# POWER.net
KiCad netlist of a schematic drawn in Altium Designer
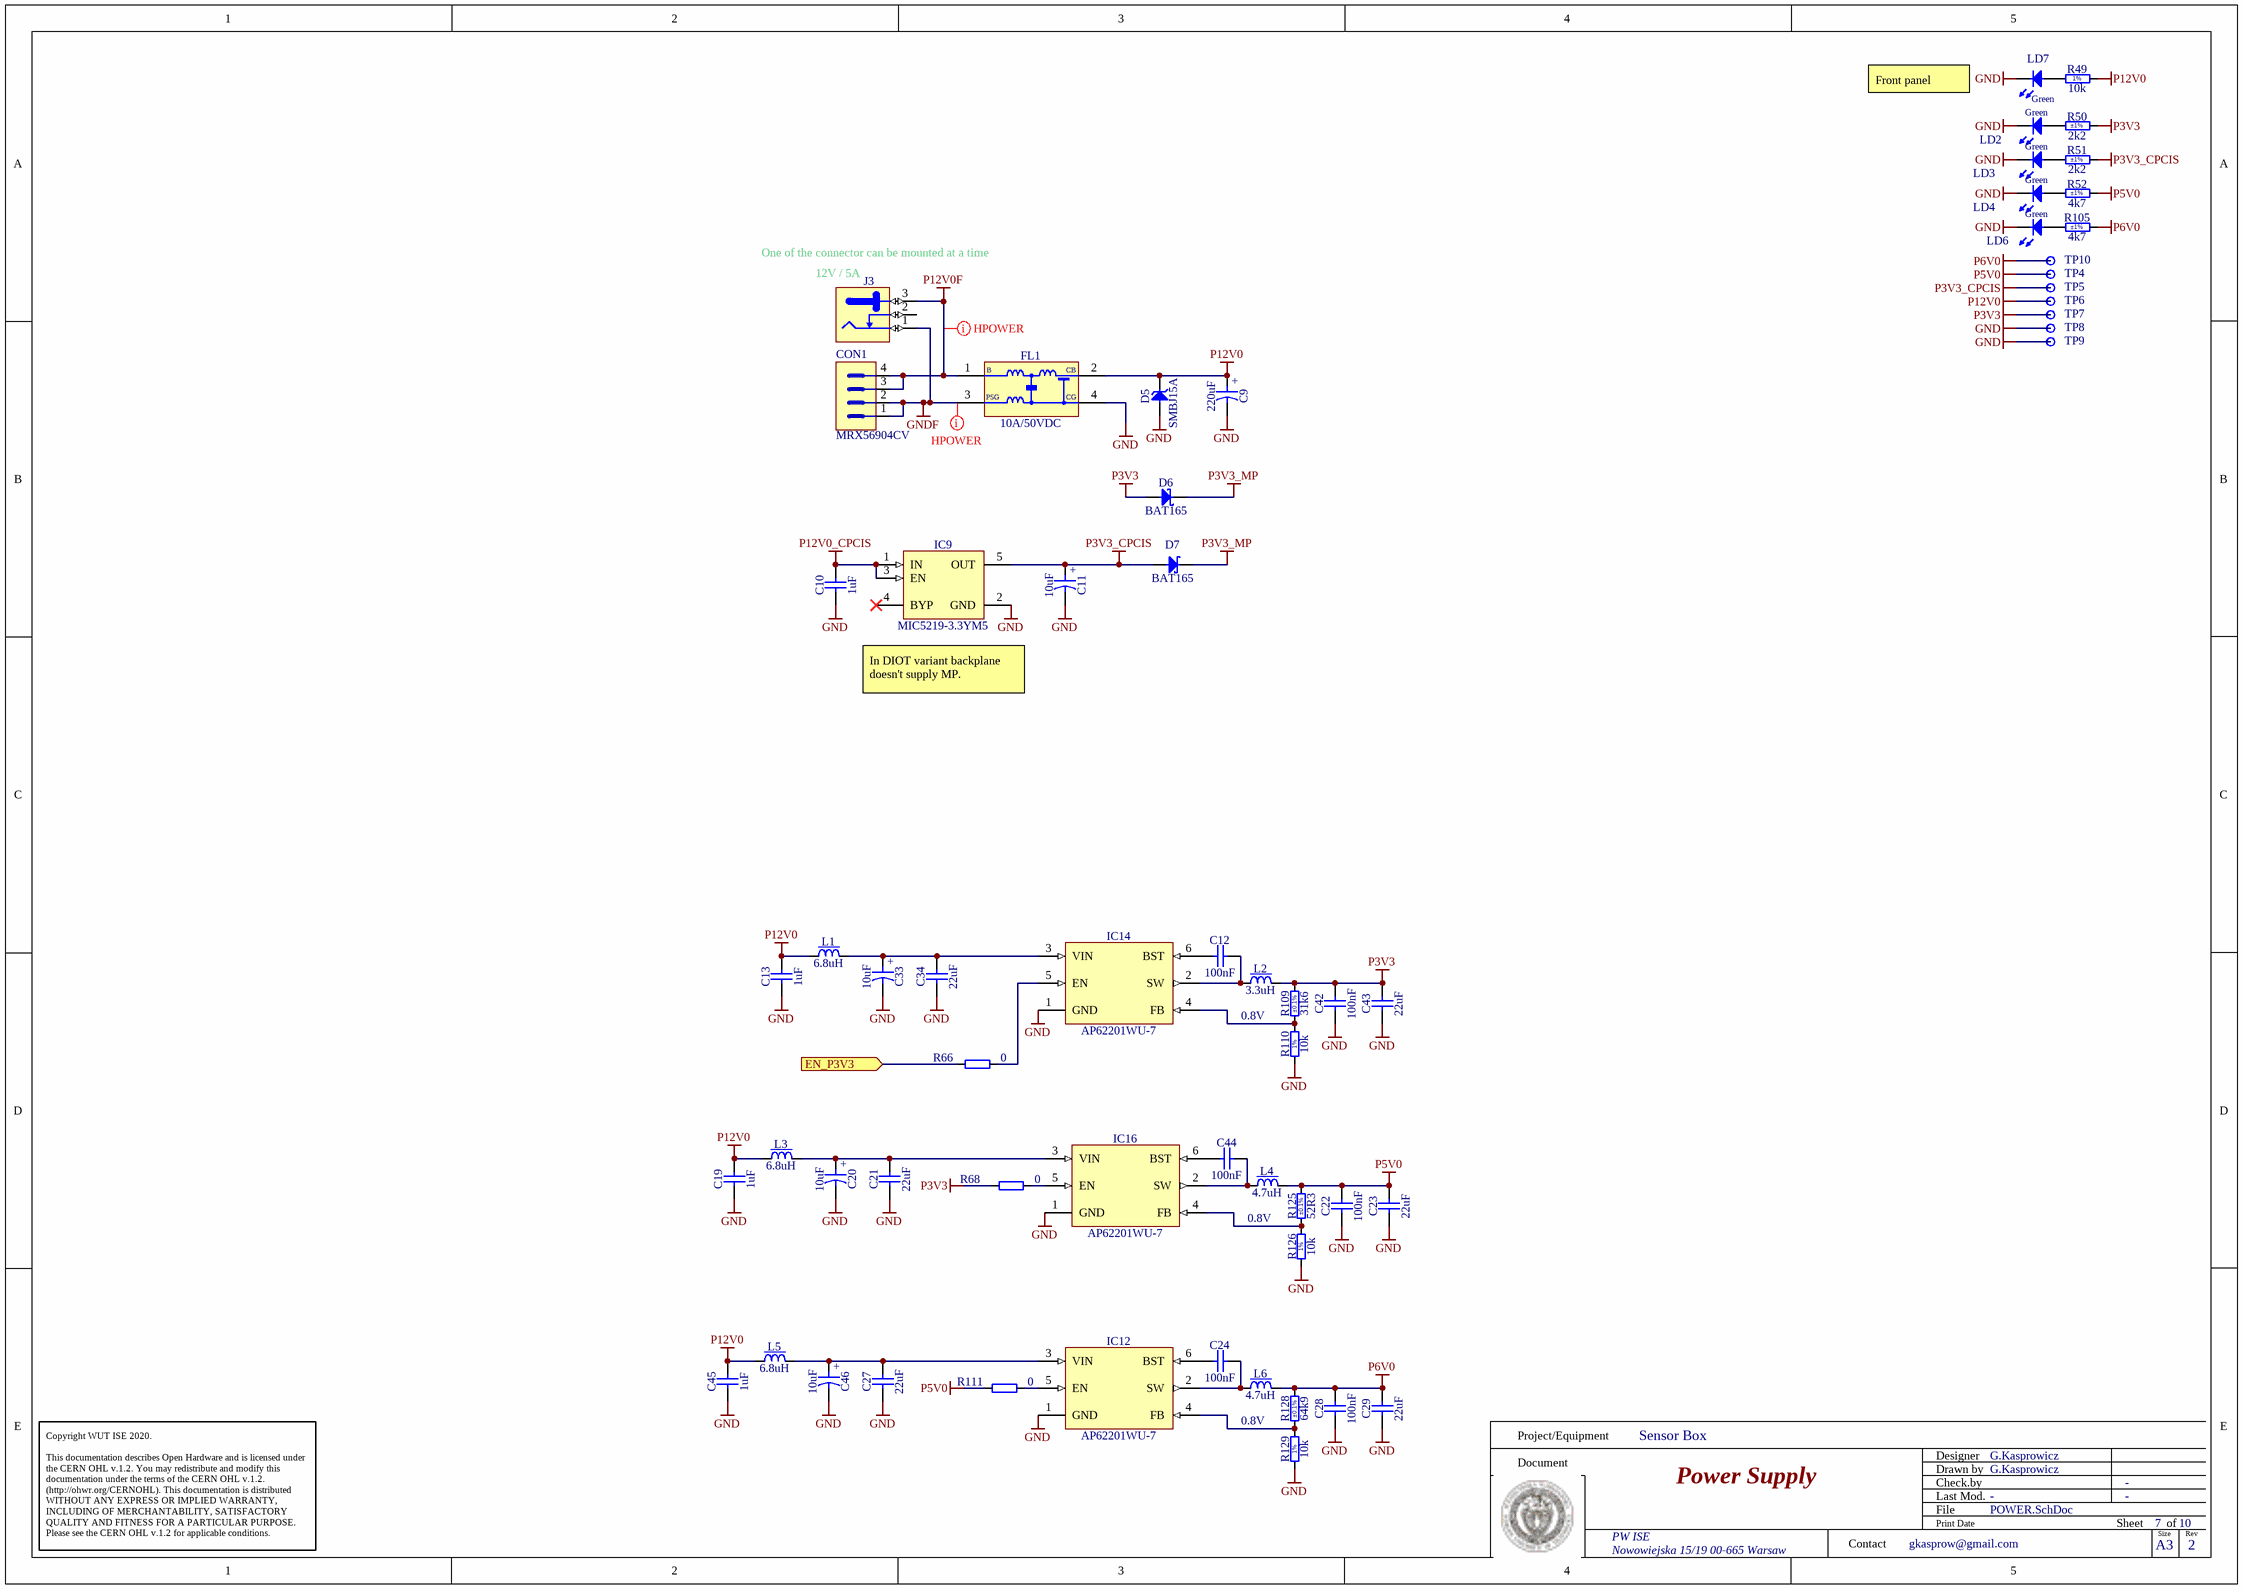
[diagram p0: POWER.SchDoc]

(export (version "E")
  (design (tool "Eeschema 10.0.6"))
  (components
    (comp (ref "C9")
      (value "220uF")
      (footprint "CAPAE830X620N")
      (description "Polarised capacitor")
      (fields
        (field (name "PART NUMBER") "CAE830-620_220UF_16V_20%")
        (field (name "VOLTAGE") "16V")
        (field (name "AUTHOR") "CERN DEM JLC")
      )
      (libsource (lib "Capacitors") (part "Capacitor - polarized"))
    )
    (comp (ref "C10")
      (value "1uF")
      (footprint "CAPC1608X87N")
      (description "Non-polarised capacitor")
      (fields
        (field (name "PART NUMBER") "CC0603_1UF_25V_10%_X7R")
        (field (name "VOLTAGE") "25V")
        (field (name "AUTHOR") "CERN DEM JLC")
      )
      (libsource (lib "Capacitors") (part "Capacitor - non polarized"))
    )
    (comp (ref "C11")
      (value "10uF")
      (footprint "CAPMP3216X180N")
      (description "Polarised capacitor")
      (fields
        (field (name "PART NUMBER") "CTE3216-18_10UF_16V_20%_AVX_TCJ")
        (field (name "VOLTAGE") "16V")
        (field (name "AUTHOR") "CERN DEM JLC")
      )
      (libsource (lib "Capacitors") (part "Capacitor - polarized"))
    )
    (comp (ref "C12")
      (value "100nF")
      (footprint "CAPC1005X55N")
      (description "Non-polarised capacitor")
      (fields
        (field (name "PART NUMBER") "CC0402_100NF_16V_10%_X5R")
        (field (name "VOLTAGE") "16V")
        (field (name "AUTHOR") "CERN DEM JLC")
      )
      (libsource (lib "Capacitors") (part "Capacitor - non polarized"))
    )
    (comp (ref "C13")
      (value "1uF")
      (footprint "CAPC1608X87N")
      (description "Non-polarised capacitor")
      (fields
        (field (name "PART NUMBER") "CC0603_1UF_25V_10%_X7R")
        (field (name "VOLTAGE") "25V")
        (field (name "AUTHOR") "CERN DEM JLC")
      )
      (libsource (lib "Capacitors") (part "Capacitor - non polarized"))
    )
    (comp (ref "C19")
      (value "1uF")
      (footprint "CAPC1608X87N")
      (description "Non-polarised capacitor")
      (fields
        (field (name "PART NUMBER") "CC0603_1UF_25V_10%_X7R")
        (field (name "VOLTAGE") "25V")
        (field (name "AUTHOR") "CERN DEM JLC")
      )
      (libsource (lib "Capacitors") (part "Capacitor - non polarized"))
    )
    (comp (ref "C20")
      (value "10uF")
      (footprint "CAPMP3216X180N")
      (description "Polarised capacitor")
      (fields
        (field (name "PART NUMBER") "CTE3216-18_10UF_16V_20%_AVX_TCJ")
        (field (name "VOLTAGE") "16V")
        (field (name "AUTHOR") "CERN DEM JLC")
      )
      (libsource (lib "Capacitors") (part "Capacitor - polarized"))
    )
    (comp (ref "C21")
      (value "22uF")
      (footprint "CAPC2012X135N")
      (description "Non-polarised capacitor")
      (fields
        (field (name "PART NUMBER") "CC0805_22UF_16V_10%_X5R")
        (field (name "VOLTAGE") "16V")
        (field (name "AUTHOR") "CERN DEM JLC")
      )
      (libsource (lib "Capacitors") (part "Capacitor - non polarized"))
    )
    (comp (ref "C22")
      (value "100nF")
      (footprint "CAPC1005X55N")
      (description "Non-polarised capacitor")
      (fields
        (field (name "PART NUMBER") "CC0402_100NF_16V_10%_X5R")
        (field (name "VOLTAGE") "16V")
        (field (name "AUTHOR") "CERN DEM JLC")
      )
      (libsource (lib "Capacitors") (part "Capacitor - non polarized"))
    )
    (comp (ref "C23")
      (value "22uF")
      (footprint "CAPC2012X135N")
      (description "Non-polarised capacitor")
      (fields
        (field (name "PART NUMBER") "CC0805_22UF_16V_10%_X5R")
        (field (name "VOLTAGE") "16V")
        (field (name "AUTHOR") "CERN DEM JLC")
      )
      (libsource (lib "Capacitors") (part "Capacitor - non polarized"))
    )
    (comp (ref "C24")
      (value "100nF")
      (footprint "CAPC1005X55N")
      (description "Non-polarised capacitor")
      (fields
        (field (name "PART NUMBER") "CC0402_100NF_16V_10%_X5R")
        (field (name "VOLTAGE") "16V")
        (field (name "AUTHOR") "CERN DEM JLC")
      )
      (libsource (lib "Capacitors") (part "Capacitor - non polarized"))
    )
    (comp (ref "C27")
      (value "22uF")
      (footprint "CAPC2012X135N")
      (description "Non-polarised capacitor")
      (fields
        (field (name "PART NUMBER") "CC0805_22UF_16V_10%_X5R")
        (field (name "VOLTAGE") "16V")
        (field (name "AUTHOR") "CERN DEM JLC")
      )
      (libsource (lib "Capacitors") (part "Capacitor - non polarized"))
    )
    (comp (ref "C28")
      (value "100nF")
      (footprint "CAPC1005X55N")
      (description "Non-polarised capacitor")
      (fields
        (field (name "PART NUMBER") "CC0402_100NF_16V_10%_X5R")
        (field (name "VOLTAGE") "16V")
        (field (name "AUTHOR") "CERN DEM JLC")
      )
      (libsource (lib "Capacitors") (part "Capacitor - non polarized"))
    )
    (comp (ref "C29")
      (value "22uF")
      (footprint "CAPC2012X135N")
      (description "Non-polarised capacitor")
      (fields
        (field (name "PART NUMBER") "CC0805_22UF_16V_10%_X5R")
        (field (name "VOLTAGE") "16V")
        (field (name "AUTHOR") "CERN DEM JLC")
      )
      (libsource (lib "Capacitors") (part "Capacitor - non polarized"))
    )
    (comp (ref "C33")
      (value "10uF")
      (footprint "CAPMP3216X180N")
      (description "Polarised capacitor")
      (fields
        (field (name "PART NUMBER") "CTE3216-18_10UF_16V_20%_AVX_TCJ")
        (field (name "VOLTAGE") "16V")
        (field (name "AUTHOR") "CERN DEM JLC")
      )
      (libsource (lib "Capacitors") (part "Capacitor - polarized"))
    )
    (comp (ref "C34")
      (value "22uF")
      (footprint "CAPC2012X135N")
      (description "Non-polarised capacitor")
      (fields
        (field (name "PART NUMBER") "CC0805_22UF_16V_10%_X5R")
        (field (name "VOLTAGE") "16V")
        (field (name "AUTHOR") "CERN DEM JLC")
      )
      (libsource (lib "Capacitors") (part "Capacitor - non polarized"))
    )
    (comp (ref "C42")
      (value "100nF")
      (footprint "CAPC1005X55N")
      (description "Non-polarised capacitor")
      (fields
        (field (name "PART NUMBER") "CC0402_100NF_16V_10%_X5R")
        (field (name "VOLTAGE") "16V")
        (field (name "AUTHOR") "CERN DEM JLC")
      )
      (libsource (lib "Capacitors") (part "Capacitor - non polarized"))
    )
    (comp (ref "C43")
      (value "22uF")
      (footprint "CAPC2012X135N")
      (description "Non-polarised capacitor")
      (fields
        (field (name "PART NUMBER") "CC0805_22UF_16V_10%_X5R")
        (field (name "VOLTAGE") "16V")
        (field (name "AUTHOR") "CERN DEM JLC")
      )
      (libsource (lib "Capacitors") (part "Capacitor - non polarized"))
    )
    (comp (ref "C44")
      (value "100nF")
      (footprint "CAPC1005X55N")
      (description "Non-polarised capacitor")
      (fields
        (field (name "PART NUMBER") "CC0402_100NF_16V_10%_X5R")
        (field (name "VOLTAGE") "16V")
        (field (name "AUTHOR") "CERN DEM JLC")
      )
      (libsource (lib "Capacitors") (part "Capacitor - non polarized"))
    )
    (comp (ref "C45")
      (value "1uF")
      (footprint "CAPC1608X87N")
      (description "Non-polarised capacitor")
      (fields
        (field (name "PART NUMBER") "CC0603_1UF_25V_10%_X7R")
        (field (name "VOLTAGE") "25V")
        (field (name "AUTHOR") "CERN DEM JLC")
      )
      (libsource (lib "Capacitors") (part "Capacitor - non polarized"))
    )
    (comp (ref "C46")
      (value "10uF")
      (footprint "CAPMP3216X180N")
      (description "Polarised capacitor")
      (fields
        (field (name "PART NUMBER") "CTE3216-18_10UF_16V_20%_AVX_TCJ")
        (field (name "VOLTAGE") "16V")
        (field (name "AUTHOR") "CERN DEM JLC")
      )
      (libsource (lib "Capacitors") (part "Capacitor - polarized"))
    )
    (comp (ref "CON1")
      (value "MRX56904CV")
      (footprint "MRX56904CV")
      (description "4.2mm cripm terminal header")
      (libsource (lib "Magneto") (part "CON_CRIMP_4.2mm_RA_4"))
    )
    (comp (ref "D5")
      (value "SMBJ15A")
      (footprint "DIOM5336X265N")
      (description "Zener Diode")
      (fields
        (field (name "VOLTAGE") "15V")
        (field (name "POWER") "600W")
        (field (name "AUTHOR") "CERN DEM JLC")
      )
      (libsource (lib "ICs And Semiconductors") (part "Diode Zener"))
    )
    (comp (ref "D6")
      (value "BAT165")
      (footprint "SOD2512X110N")
      (description "Schottky Diode")
      (fields
        (field (name "VOLTAGE") "40V")
        (field (name "POWER") "750mA")
        (field (name "AUTHOR") "CERN DEM JLC")
      )
      (libsource (lib "ICs And Semiconductors") (part "Diode Schottky"))
    )
    (comp (ref "D7")
      (value "BAT165")
      (footprint "SOD2512X110N")
      (description "Schottky Diode")
      (fields
        (field (name "MANUFACTURER") "INFINEON")
        (field (name "VOLTAGE") "40V")
        (field (name "AUTHOR") "CERN DEM JLC")
      )
      (libsource (lib "ICs And Semiconductors") (part "Diode Schottky"))
    )
    (comp (ref "FL1")
      (value "10A/50VDC")
      (footprint "FIL_MURATA_BNX02")
      (description "Block Type EMIFIL (LC Combined)")
      (fields
        (field (name "PART NUMBER") "FIL_MURATA_BNX022-01L")
        (field (name "MANUFACTURER") "MURATA")
        (field (name "AUTHOR") "CERN DEM JLC")
      )
      (libsource (lib "Inductors & Transformers") (part "FIL_MURATA_BNX02"))
    )
    (comp (ref "IC9")
      (value "MIC5219-3.3YM5")
      (footprint "SOT95P280X145-5N")
      (description "500mA Peak Output LDO Regulator")
      (fields (field (name "MANUFACTURER") "MICROCHIP TECHNOLOGY") (field (name "AUTHOR") "CERN DEM WB"))
      (libsource (lib "ICs And Semiconductors") (part "MIC5219-X.XYM5"))
    )
    (comp (ref "IC12")
      (value "AP62201WU-7")
      (footprint "SOT95P280X100-6N")
      (description "4.2V TO 18V INPUT, 2A LOW IQ SYNCHRONOUS BUCK CONVERTER")
      (fields (field (name "MANUFACTURER") "DIODES INCORPORATED") (field (name "AUTHOR") "CERN DEM HF"))
      (libsource (lib "Magneto") (part "AP62201WU-7"))
    )
    (comp (ref "IC14")
      (value "AP62201WU-7")
      (footprint "SOT95P280X100-6N")
      (description "4.2V TO 18V INPUT, 2A LOW IQ SYNCHRONOUS BUCK CONVERTER")
      (fields (field (name "MANUFACTURER") "DIODES INCORPORATED") (field (name "AUTHOR") "CERN DEM HF"))
      (libsource (lib "Magneto") (part "AP62201WU-7"))
    )
    (comp (ref "IC16")
      (value "AP62201WU-7")
      (footprint "SOT95P280X100-6N")
      (description "4.2V TO 18V INPUT, 2A LOW IQ SYNCHRONOUS BUCK CONVERTER")
      (fields (field (name "MANUFACTURER") "DIODES INCORPORATED") (field (name "AUTHOR") "CERN DEM HF"))
      (libsource (lib "Magneto") (part "AP62201WU-7"))
    )
    (comp (ref "J3")
      (value "Jack")
      (footprint "SWITCHCRAFT_L712RA")
      (description "24V /3. 5A, 2.1mm Diameter Pin, SMD DC Power Supply Connector With  Break Contact")
      (fields
        (field (name "PART NUMBER") "SWITCHCRAFT_L712RA")
        (field (name "MANUFACTURER") "SWITCHCRAFT")
        (field (name "AUTHOR") "GK")
      )
      (libsource (lib "LIBRARY_SCH") (part "CON_DC_5A_THT_RA"))
    )
    (comp (ref "L1")
      (value "6.8uH")
      (footprint "IND_COILCRAFT_XAL4030")
      (description "Inductor With Core")
      (fields
        (field (name "PART NUMBER") "IND_6.8UH_20%_COILCRAFT_XAL4030")
        (field (name "POWER") "3A")
        (field (name "AUTHOR") "CERN DEM MR")
      )
      (libsource (lib "Inductors & Transformers") (part "Inductor With Magnetic core"))
    )
    (comp (ref "L2")
      (value "3.3uH")
      (footprint "IND_WURTH_WE-TPC_4828")
      (description "Inductor With Core")
      (fields
        (field (name "PART NUMBER") "IND_3.3UH_30%_WURTH_WE-TPC_744043003")
        (field (name "POWER") "2.15A")
        (field (name "AUTHOR") "CERN DEM JLC")
      )
      (libsource (lib "Inductors & Transformers") (part "Inductor With Magnetic core"))
    )
    (comp (ref "L3")
      (value "6.8uH")
      (footprint "IND_COILCRAFT_XAL4030")
      (description "Inductor With Core")
      (fields
        (field (name "PART NUMBER") "IND_6.8UH_20%_COILCRAFT_XAL4030")
        (field (name "POWER") "3A")
        (field (name "AUTHOR") "CERN DEM MR")
      )
      (libsource (lib "Inductors & Transformers") (part "Inductor With Magnetic core"))
    )
    (comp (ref "L4")
      (value "4.7uH")
      (footprint "IND_WURTH_WE-SPC-4838")
      (description "Inductor With Core")
      (fields
        (field (name "PART NUMBER") "IND_4.7UH_20%_WURTH_WE-SPC_74408943047")
        (field (name "POWER") "2.2A")
        (field (name "AUTHOR") "CERN DEM JLC")
      )
      (libsource (lib "Inductors & Transformers") (part "Inductor With Magnetic core"))
    )
    (comp (ref "L5")
      (value "6.8uH")
      (footprint "IND_COILCRAFT_XAL4030")
      (description "Inductor With Core")
      (fields
        (field (name "PART NUMBER") "IND_6.8UH_20%_COILCRAFT_XAL4030")
        (field (name "POWER") "3A")
        (field (name "AUTHOR") "CERN DEM MR")
      )
      (libsource (lib "Inductors & Transformers") (part "Inductor With Magnetic core"))
    )
    (comp (ref "L6")
      (value "4.7uH")
      (footprint "IND_WURTH_WE-SPC-4838")
      (description "Inductor With Core")
      (fields
        (field (name "PART NUMBER") "IND_4.7UH_20%_WURTH_WE-SPC_74408943047")
        (field (name "POWER") "2.2A")
        (field (name "AUTHOR") "CERN DEM JLC")
      )
      (libsource (lib "Inductors & Transformers") (part "Inductor With Magnetic core"))
    )
    (comp (ref "LD2")
      (value "Green")
      (footprint "LED_KINGBRIGHT_KPH-1608CGCK")
      (description "LED Green 1C 2A")
      (fields
        (field (name "PART NUMBER") "LED_KINGBRIGHT_KPH-1608CGCK")
        (field (name "MANUFACTURER") "KINGBRIGHT")
        (field (name "AUTHOR") "CERN DEM JLC")
      )
      (libsource (lib "ICs And Semiconductors") (part "LED Green 1C 2A"))
    )
    (comp (ref "LD3")
      (value "Green")
      (footprint "LED_KINGBRIGHT_KPH-1608CGCK")
      (description "LED Green 1C 2A")
      (fields
        (field (name "PART NUMBER") "LED_KINGBRIGHT_KPH-1608CGCK")
        (field (name "MANUFACTURER") "KINGBRIGHT")
        (field (name "AUTHOR") "CERN DEM JLC")
      )
      (libsource (lib "ICs And Semiconductors") (part "LED Green 1C 2A"))
    )
    (comp (ref "LD4")
      (value "Green")
      (footprint "LED_KINGBRIGHT_KPH-1608CGCK")
      (description "LED Green 1C 2A")
      (fields
        (field (name "PART NUMBER") "LED_KINGBRIGHT_KPH-1608CGCK")
        (field (name "MANUFACTURER") "KINGBRIGHT")
        (field (name "AUTHOR") "CERN DEM JLC")
      )
      (libsource (lib "ICs And Semiconductors") (part "LED Green 1C 2A"))
    )
    (comp (ref "LD6")
      (value "Green")
      (footprint "LED_KINGBRIGHT_KPH-1608CGCK")
      (description "LED Green 1C 2A")
      (fields
        (field (name "PART NUMBER") "LED_KINGBRIGHT_KPH-1608CGCK")
        (field (name "MANUFACTURER") "KINGBRIGHT")
        (field (name "AUTHOR") "CERN DEM JLC")
      )
      (libsource (lib "ICs And Semiconductors") (part "LED Green 1C 2A"))
    )
    (comp (ref "LD7")
      (value "Green")
      (footprint "LED_DIALIGHT_555-230")
      (description "LED Green 1C 2A")
      (fields
        (field (name "PART NUMBER") "LED_DIALIGHT_555-2301F")
        (field (name "MANUFACTURER") "DIALIGHT")
        (field (name "AUTHOR") "CERN DEM JMW")
      )
      (libsource (lib "ICs And Semiconductors") (part "LED Green 1C 2A"))
    )
    (comp (ref "R49")
      (value "10k")
      (footprint "RESC1005X40N")
      (description "Resistor - 1%")
      (fields
        (field (name "PART NUMBER") "R0402_10K_1%_0.0625W_100PPM")
        (field (name "POWER") "0.0625W")
        (field (name "AUTHOR") "CERN DEM JLC")
      )
      (libsource (lib "Resistors") (part "Resistor - 1%"))
    )
    (comp (ref "R50")
      (value "2k2")
      (footprint "RESC1005X40N")
      (description "Resistor - 1%")
      (fields
        (field (name "TOLERANCE") "±1%")
        (field (name "PART NUMBER") "R0402_2K2_1%_0.0625W_100PPM")
        (field (name "POWER") "0.0625W")
        (field (name "AUTHOR") "CERN DEM JLC")
      )
      (libsource (lib "Resistors") (part "Resistor - 1%"))
    )
    (comp (ref "R51")
      (value "2k2")
      (footprint "RESC1005X40N")
      (description "Resistor - 1%")
      (fields
        (field (name "TOLERANCE") "±1%")
        (field (name "PART NUMBER") "R0402_2K2_1%_0.0625W_100PPM")
        (field (name "POWER") "0.0625W")
        (field (name "AUTHOR") "CERN DEM JLC")
      )
      (libsource (lib "Resistors") (part "Resistor - 1%"))
    )
    (comp (ref "R52")
      (value "4k7")
      (footprint "RESC1005X40N")
      (description "Resistor - 1%")
      (fields
        (field (name "TOLERANCE") "±1%")
        (field (name "PART NUMBER") "R0402_4K7_1%_0.0625W_100PPM")
        (field (name "POWER") "0.0625W")
        (field (name "AUTHOR") "CERN DEM JLC")
      )
      (libsource (lib "Resistors") (part "Resistor - 1%"))
    )
    (comp (ref "R66")
      (value "0")
      (footprint "RESC1005X40N")
      (description "Resistor")
      (fields
        (field (name "PART NUMBER") "R0402_0R_JUMPER")
        (field (name "MANUFACTURER") "GENERIC")
        (field (name "AUTHOR") "CERN DEM JLC")
      )
      (libsource (lib "Resistors") (part "Resistor"))
    )
    (comp (ref "R68")
      (value "0")
      (footprint "RESC1005X40N")
      (description "Resistor")
      (fields
        (field (name "PART NUMBER") "R0402_0R_JUMPER")
        (field (name "MANUFACTURER") "GENERIC")
        (field (name "AUTHOR") "CERN DEM JLC")
      )
      (libsource (lib "Resistors") (part "Resistor"))
    )
    (comp (ref "R105")
      (value "4k7")
      (footprint "RESC1005X40N")
      (description "Resistor - 1%")
      (fields
        (field (name "TOLERANCE") "±1%")
        (field (name "PART NUMBER") "R0402_4K7_1%_0.0625W_100PPM")
        (field (name "POWER") "0.0625W")
        (field (name "AUTHOR") "CERN DEM JLC")
      )
      (libsource (lib "Resistors") (part "Resistor - 1%"))
    )
    (comp (ref "R109")
      (value "31k6")
      (footprint "RESC1005X35N")
      (description "Resistor - 0.1%")
      (fields
        (field (name "TOLERANCE") "±0.1%")
        (field (name "PART NUMBER") "R0402_31K6_0.1%_0.063W_25PPM_YAGEO_RT")
        (field (name "POWER") "0.063W")
        (field (name "AUTHOR") "CERN DEM BC")
      )
      (libsource (lib "Resistors") (part "Resistor - 0.1%"))
    )
    (comp (ref "R110")
      (value "10k")
      (footprint "RESC1005X40N")
      (description "Resistor - 1%")
      (fields
        (field (name "PART NUMBER") "R0402_10K_1%_0.0625W_100PPM")
        (field (name "POWER") "0.0625W")
        (field (name "AUTHOR") "CERN DEM JLC")
      )
      (libsource (lib "Resistors") (part "Resistor - 1%"))
    )
    (comp (ref "R111")
      (value "0")
      (footprint "RESC1005X40N")
      (description "Resistor")
      (fields
        (field (name "PART NUMBER") "R0402_0R_JUMPER")
        (field (name "MANUFACTURER") "GENERIC")
        (field (name "AUTHOR") "CERN DEM JLC")
      )
      (libsource (lib "Resistors") (part "Resistor"))
    )
    (comp (ref "R125")
      (value "52R3")
      (footprint "RESC1608X55N")
      (description "Resistor - 0.1%")
      (fields
        (field (name "TOLERANCE") "±0.1%")
        (field (name "PART NUMBER") "R0603_52R3_0.1%_0.063W_10PPM")
        (field (name "POWER") "0.063W")
        (field (name "AUTHOR") "CERN DEM JLC")
      )
      (libsource (lib "Resistors") (part "Resistor - 0.1%"))
    )
    (comp (ref "R126")
      (value "10k")
      (footprint "RESC1005X40N")
      (description "Resistor - 1%")
      (fields
        (field (name "PART NUMBER") "R0402_10K_1%_0.0625W_100PPM")
        (field (name "POWER") "0.0625W")
        (field (name "AUTHOR") "CERN DEM JLC")
      )
      (libsource (lib "Resistors") (part "Resistor - 1%"))
    )
    (comp (ref "R128")
      (value "64k9")
      (footprint "RESC1005X40N")
      (description "Resistor - 0.1%")
      (fields
        (field (name "TOLERANCE") "±0.1%")
        (field (name "PART NUMBER") "R0402_64K9_0.1%_0.063W_25PPM")
        (field (name "POWER") "0.063W")
        (field (name "AUTHOR") "CERN DEM HF")
      )
      (libsource (lib "Resistors") (part "Resistor - 0.1%"))
    )
    (comp (ref "R129")
      (value "10k")
      (footprint "RESC1005X40N")
      (description "Resistor - 1%")
      (fields
        (field (name "PART NUMBER") "R0402_10K_1%_0.0625W_100PPM")
        (field (name "POWER") "0.0625W")
        (field (name "AUTHOR") "CERN DEM JLC")
      )
      (libsource (lib "Resistors") (part "Resistor - 1%"))
    )
    (comp (ref "TP4")
      (value "Plated Hole")
      (footprint "c150h100")
      (description "Single Terminal Socket")
      (fields (field (name "PART NUMBER") "PLATED_HOLE1.0_PAD1.5") (field (name "AUTHOR") "CERN DEM JLC"))
      (libsource (lib "Eletro-mechanical") (part "Single Terminal Socket"))
    )
    (comp (ref "TP5")
      (value "Plated Hole")
      (footprint "c150h100")
      (description "Single Terminal Socket")
      (fields (field (name "PART NUMBER") "PLATED_HOLE1.0_PAD1.5") (field (name "AUTHOR") "CERN DEM JLC"))
      (libsource (lib "Eletro-mechanical") (part "Single Terminal Socket"))
    )
    (comp (ref "TP6")
      (value "Plated Hole")
      (footprint "c150h100")
      (description "Single Terminal Socket")
      (fields (field (name "PART NUMBER") "PLATED_HOLE1.0_PAD1.5") (field (name "AUTHOR") "CERN DEM JLC"))
      (libsource (lib "Eletro-mechanical") (part "Single Terminal Socket"))
    )
    (comp (ref "TP7")
      (value "Plated Hole")
      (footprint "c150h100")
      (description "Single Terminal Socket")
      (fields (field (name "PART NUMBER") "PLATED_HOLE1.0_PAD1.5") (field (name "AUTHOR") "CERN DEM JLC"))
      (libsource (lib "Eletro-mechanical") (part "Single Terminal Socket"))
    )
    (comp (ref "TP8")
      (value "Plated Hole")
      (footprint "c150h100")
      (description "Single Terminal Socket")
      (fields (field (name "PART NUMBER") "PLATED_HOLE1.0_PAD1.5") (field (name "AUTHOR") "CERN DEM JLC"))
      (libsource (lib "Eletro-mechanical") (part "Single Terminal Socket"))
    )
    (comp (ref "TP9")
      (value "Plated Hole")
      (footprint "c150h100")
      (description "Single Terminal Socket")
      (fields (field (name "PART NUMBER") "PLATED_HOLE1.0_PAD1.5") (field (name "AUTHOR") "CERN DEM JLC"))
      (libsource (lib "Eletro-mechanical") (part "Single Terminal Socket"))
    )
    (comp (ref "TP10")
      (value "Plated Hole")
      (footprint "c150h100")
      (description "Single Terminal Socket")
      (fields (field (name "PART NUMBER") "PLATED_HOLE1.0_PAD1.5") (field (name "AUTHOR") "CERN DEM JLC"))
      (libsource (lib "Eletro-mechanical") (part "Single Terminal Socket"))
    )
  )
  (nets
    (net (code "1") (name "/EN_P3V3") (class "Default")
      (node (ref "R66") (pin "1") (pinfunction "1_1") (pintype "passive"))
    )
    (net (code "2") (name "GND") (class "Default")
      (node (ref "C10") (pin "1") (pinfunction "1_1") (pintype "passive"))
      (node (ref "C11") (pin "2") (pinfunction "2_2") (pintype "passive"))
      (node (ref "C13") (pin "1") (pinfunction "1_1") (pintype "passive"))
      (node (ref "C19") (pin "1") (pinfunction "1_1") (pintype "passive"))
      (node (ref "C20") (pin "2") (pinfunction "2_2") (pintype "passive"))
      (node (ref "C21") (pin "1") (pinfunction "1_1") (pintype "passive"))
      (node (ref "C22") (pin "1") (pinfunction "1_1") (pintype "passive"))
      (node (ref "C23") (pin "1") (pinfunction "1_1") (pintype "passive"))
      (node (ref "C27") (pin "1") (pinfunction "1_1") (pintype "passive"))
      (node (ref "C28") (pin "1") (pinfunction "1_1") (pintype "passive"))
      (node (ref "C29") (pin "1") (pinfunction "1_1") (pintype "passive"))
      (node (ref "C33") (pin "2") (pinfunction "2_2") (pintype "passive"))
      (node (ref "C34") (pin "1") (pinfunction "1_1") (pintype "passive"))
      (node (ref "C42") (pin "1") (pinfunction "1_1") (pintype "passive"))
      (node (ref "C43") (pin "1") (pinfunction "1_1") (pintype "passive"))
      (node (ref "C45") (pin "1") (pinfunction "1_1") (pintype "passive"))
      (node (ref "C46") (pin "2") (pinfunction "2_2") (pintype "passive"))
      (node (ref "C9") (pin "2") (pinfunction "2_2") (pintype "passive"))
      (node (ref "D5") (pin "2") (pinfunction "A_2") (pintype "passive"))
      (node (ref "FL1") (pin "4") (pinfunction "CG_4") (pintype "passive"))
      (node (ref "IC12") (pin "1") (pinfunction "GND_1") (pintype "power_in"))
      (node (ref "IC14") (pin "1") (pinfunction "GND_1") (pintype "power_in"))
      (node (ref "IC16") (pin "1") (pinfunction "GND_1") (pintype "power_in"))
      (node (ref "IC9") (pin "2") (pinfunction "GND_2") (pintype "power_in"))
      (node (ref "LD2") (pin "1") (pinfunction "C_1") (pintype "passive"))
      (node (ref "LD3") (pin "1") (pinfunction "C_1") (pintype "passive"))
      (node (ref "LD4") (pin "1") (pinfunction "C_1") (pintype "passive"))
      (node (ref "LD6") (pin "1") (pinfunction "C_1") (pintype "passive"))
      (node (ref "LD7") (pin "1") (pinfunction "C_1") (pintype "passive"))
      (node (ref "R110") (pin "1") (pinfunction "1_1") (pintype "passive"))
      (node (ref "R126") (pin "1") (pinfunction "1_1") (pintype "passive"))
      (node (ref "R129") (pin "1") (pinfunction "1_1") (pintype "passive"))
      (node (ref "TP8") (pin "1") (pinfunction "1_1") (pintype "bidirectional"))
      (node (ref "TP9") (pin "1") (pinfunction "1_1") (pintype "bidirectional"))
    )
    (net (code "3") (name "GNDF") (class "Default")
      (node (ref "CON1") (pin "1") (pinfunction "1_1") (pintype "bidirectional"))
      (node (ref "CON1") (pin "2") (pinfunction "2_2") (pintype "bidirectional"))
      (node (ref "FL1") (pin "3") (pinfunction "PSG_3") (pintype "passive"))
      (node (ref "J3") (pin "1") (pinfunction "1_1") (pintype "bidirectional"))
    )
    (net (code "4") (name "Net-(IC12-BST)") (class "Default")
      (node (ref "C24") (pin "1") (pinfunction "1_1") (pintype "passive"))
      (node (ref "IC12") (pin "6") (pinfunction "BST_6") (pintype "input"))
    )
    (net (code "5") (name "Net-(IC12-EN)") (class "Default")
      (node (ref "IC12") (pin "5") (pinfunction "EN_5") (pintype "input"))
      (node (ref "R111") (pin "2") (pinfunction "2_2") (pintype "passive"))
    )
    (net (code "6") (name "Net-(IC12-FB)") (class "Default")
      (node (ref "IC12") (pin "4") (pinfunction "FB_4") (pintype "input"))
      (node (ref "R128") (pin "1") (pinfunction "1_1") (pintype "passive"))
      (node (ref "R129") (pin "2") (pinfunction "2_2") (pintype "passive"))
    )
    (net (code "7") (name "Net-(IC12-SW)") (class "Default")
      (node (ref "C24") (pin "2") (pinfunction "2_2") (pintype "passive"))
      (node (ref "IC12") (pin "2") (pinfunction "SW_2") (pintype "output"))
      (node (ref "L6") (pin "1") (pinfunction "1_1") (pintype "passive"))
    )
    (net (code "8") (name "Net-(IC12-VIN)") (class "Default")
      (node (ref "C27") (pin "2") (pinfunction "2_2") (pintype "passive"))
      (node (ref "C46") (pin "1") (pinfunction "1_1") (pintype "passive"))
      (node (ref "IC12") (pin "3") (pinfunction "VIN_3") (pintype "input"))
      (node (ref "L5") (pin "2") (pinfunction "2_2") (pintype "passive"))
    )
    (net (code "9") (name "Net-(IC14-BST)") (class "Default")
      (node (ref "C12") (pin "1") (pinfunction "1_1") (pintype "passive"))
      (node (ref "IC14") (pin "6") (pinfunction "BST_6") (pintype "input"))
    )
    (net (code "10") (name "Net-(IC14-EN)") (class "Default")
      (node (ref "IC14") (pin "5") (pinfunction "EN_5") (pintype "input"))
      (node (ref "R66") (pin "2") (pinfunction "2_2") (pintype "passive"))
    )
    (net (code "11") (name "Net-(IC14-FB)") (class "Default")
      (node (ref "IC14") (pin "4") (pinfunction "FB_4") (pintype "input"))
      (node (ref "R109") (pin "1") (pinfunction "1_1") (pintype "passive"))
      (node (ref "R110") (pin "2") (pinfunction "2_2") (pintype "passive"))
    )
    (net (code "12") (name "Net-(IC14-SW)") (class "Default")
      (node (ref "C12") (pin "2") (pinfunction "2_2") (pintype "passive"))
      (node (ref "IC14") (pin "2") (pinfunction "SW_2") (pintype "output"))
      (node (ref "L2") (pin "1") (pinfunction "1_1") (pintype "passive"))
    )
    (net (code "13") (name "Net-(IC14-VIN)") (class "Default")
      (node (ref "C33") (pin "1") (pinfunction "1_1") (pintype "passive"))
      (node (ref "C34") (pin "2") (pinfunction "2_2") (pintype "passive"))
      (node (ref "IC14") (pin "3") (pinfunction "VIN_3") (pintype "input"))
      (node (ref "L1") (pin "2") (pinfunction "2_2") (pintype "passive"))
    )
    (net (code "14") (name "Net-(IC16-BST)") (class "Default")
      (node (ref "C44") (pin "1") (pinfunction "1_1") (pintype "passive"))
      (node (ref "IC16") (pin "6") (pinfunction "BST_6") (pintype "input"))
    )
    (net (code "15") (name "Net-(IC16-EN)") (class "Default")
      (node (ref "IC16") (pin "5") (pinfunction "EN_5") (pintype "input"))
      (node (ref "R68") (pin "2") (pinfunction "2_2") (pintype "passive"))
    )
    (net (code "16") (name "Net-(IC16-FB)") (class "Default")
      (node (ref "IC16") (pin "4") (pinfunction "FB_4") (pintype "input"))
      (node (ref "R125") (pin "1") (pinfunction "1_1") (pintype "passive"))
      (node (ref "R126") (pin "2") (pinfunction "2_2") (pintype "passive"))
    )
    (net (code "17") (name "Net-(IC16-SW)") (class "Default")
      (node (ref "C44") (pin "2") (pinfunction "2_2") (pintype "passive"))
      (node (ref "IC16") (pin "2") (pinfunction "SW_2") (pintype "output"))
      (node (ref "L4") (pin "1") (pinfunction "1_1") (pintype "passive"))
    )
    (net (code "18") (name "Net-(IC16-VIN)") (class "Default")
      (node (ref "C20") (pin "1") (pinfunction "1_1") (pintype "passive"))
      (node (ref "C21") (pin "2") (pinfunction "2_2") (pintype "passive"))
      (node (ref "IC16") (pin "3") (pinfunction "VIN_3") (pintype "input"))
      (node (ref "L3") (pin "2") (pinfunction "2_2") (pintype "passive"))
    )
    (net (code "19") (name "Net-(LD2-A)") (class "Default")
      (node (ref "LD2") (pin "2") (pinfunction "A_2") (pintype "passive"))
      (node (ref "R50") (pin "1") (pinfunction "1_1") (pintype "passive"))
    )
    (net (code "20") (name "Net-(LD3-A)") (class "Default")
      (node (ref "LD3") (pin "2") (pinfunction "A_2") (pintype "passive"))
      (node (ref "R51") (pin "1") (pinfunction "1_1") (pintype "passive"))
    )
    (net (code "21") (name "Net-(LD4-A)") (class "Default")
      (node (ref "LD4") (pin "2") (pinfunction "A_2") (pintype "passive"))
      (node (ref "R52") (pin "1") (pinfunction "1_1") (pintype "passive"))
    )
    (net (code "22") (name "Net-(LD6-A)") (class "Default")
      (node (ref "LD6") (pin "2") (pinfunction "A_2") (pintype "passive"))
      (node (ref "R105") (pin "1") (pinfunction "1_1") (pintype "passive"))
    )
    (net (code "23") (name "Net-(LD7-A)") (class "Default")
      (node (ref "LD7") (pin "2") (pinfunction "A_2") (pintype "passive"))
      (node (ref "R49") (pin "1") (pinfunction "1_1") (pintype "passive"))
    )
    (net (code "24") (name "P3V3") (class "Default")
      (node (ref "C42") (pin "2") (pinfunction "2_2") (pintype "passive"))
      (node (ref "C43") (pin "2") (pinfunction "2_2") (pintype "passive"))
      (node (ref "D6") (pin "2") (pinfunction "A_2") (pintype "passive"))
      (node (ref "L2") (pin "2") (pinfunction "2_2") (pintype "passive"))
      (node (ref "R109") (pin "2") (pinfunction "2_2") (pintype "passive"))
      (node (ref "R50") (pin "2") (pinfunction "2_2") (pintype "passive"))
      (node (ref "R68") (pin "1") (pinfunction "1_1") (pintype "passive"))
      (node (ref "TP7") (pin "1") (pinfunction "1_1") (pintype "bidirectional"))
    )
    (net (code "25") (name "P3V3_CPCIS") (class "Default")
      (node (ref "C11") (pin "1") (pinfunction "1_1") (pintype "passive"))
      (node (ref "D7") (pin "2") (pinfunction "A_2") (pintype "passive"))
      (node (ref "IC9") (pin "5") (pinfunction "OUT_5") (pintype "power_in"))
      (node (ref "R51") (pin "2") (pinfunction "2_2") (pintype "passive"))
      (node (ref "TP5") (pin "1") (pinfunction "1_1") (pintype "bidirectional"))
    )
    (net (code "26") (name "P3V3_MP") (class "Default")
      (node (ref "D6") (pin "1") (pinfunction "C_1") (pintype "passive"))
      (node (ref "D7") (pin "1") (pinfunction "C_1") (pintype "passive"))
    )
    (net (code "27") (name "P5V0") (class "Default")
      (node (ref "C22") (pin "2") (pinfunction "2_2") (pintype "passive"))
      (node (ref "C23") (pin "2") (pinfunction "2_2") (pintype "passive"))
      (node (ref "L4") (pin "2") (pinfunction "2_2") (pintype "passive"))
      (node (ref "R111") (pin "1") (pinfunction "1_1") (pintype "passive"))
      (node (ref "R125") (pin "2") (pinfunction "2_2") (pintype "passive"))
      (node (ref "R52") (pin "2") (pinfunction "2_2") (pintype "passive"))
      (node (ref "TP4") (pin "1") (pinfunction "1_1") (pintype "bidirectional"))
    )
    (net (code "28") (name "P6V0") (class "Default")
      (node (ref "C28") (pin "2") (pinfunction "2_2") (pintype "passive"))
      (node (ref "C29") (pin "2") (pinfunction "2_2") (pintype "passive"))
      (node (ref "L6") (pin "2") (pinfunction "2_2") (pintype "passive"))
      (node (ref "R105") (pin "2") (pinfunction "2_2") (pintype "passive"))
      (node (ref "R128") (pin "2") (pinfunction "2_2") (pintype "passive"))
      (node (ref "TP10") (pin "1") (pinfunction "1_1") (pintype "bidirectional"))
    )
    (net (code "29") (name "P12V0") (class "Default")
      (node (ref "C13") (pin "2") (pinfunction "2_2") (pintype "passive"))
      (node (ref "C19") (pin "2") (pinfunction "2_2") (pintype "passive"))
      (node (ref "C45") (pin "2") (pinfunction "2_2") (pintype "passive"))
      (node (ref "C9") (pin "1") (pinfunction "1_1") (pintype "passive"))
      (node (ref "D5") (pin "1") (pinfunction "C_1") (pintype "passive"))
      (node (ref "FL1") (pin "2") (pinfunction "CB_2") (pintype "passive"))
      (node (ref "L1") (pin "1") (pinfunction "1_1") (pintype "passive"))
      (node (ref "L3") (pin "1") (pinfunction "1_1") (pintype "passive"))
      (node (ref "L5") (pin "1") (pinfunction "1_1") (pintype "passive"))
      (node (ref "R49") (pin "2") (pinfunction "2_2") (pintype "passive"))
      (node (ref "TP6") (pin "1") (pinfunction "1_1") (pintype "bidirectional"))
    )
    (net (code "30") (name "P12V0F") (class "Default")
      (node (ref "CON1") (pin "3") (pinfunction "3_3") (pintype "bidirectional"))
      (node (ref "CON1") (pin "4") (pinfunction "4_4") (pintype "bidirectional"))
      (node (ref "FL1") (pin "1") (pinfunction "B_1") (pintype "passive"))
      (node (ref "J3") (pin "3") (pinfunction "3_3") (pintype "bidirectional"))
    )
    (net (code "31") (name "P12V0_CPCIS") (class "Default")
      (node (ref "C10") (pin "2") (pinfunction "2_2") (pintype "passive"))
      (node (ref "IC9") (pin "1") (pinfunction "IN_1") (pintype "input"))
      (node (ref "IC9") (pin "3") (pinfunction "EN_3") (pintype "input"))
    )
    (net (code "32") (name "unconnected-(IC9-BYP-Pad4)") (class "Default")
      (node (ref "IC9") (pin "4") (pinfunction "BYP_4") (pintype "passive+no_connect"))
    )
    (net (code "33") (name "unconnected-(J3-Pad2)") (class "Default")
      (node (ref "J3") (pin "2") (pinfunction "2_2") (pintype "bidirectional"))
    )
  )
)
